# Motor_Driver.net
KiCad netlist of a schematic drawn in Altium Designer
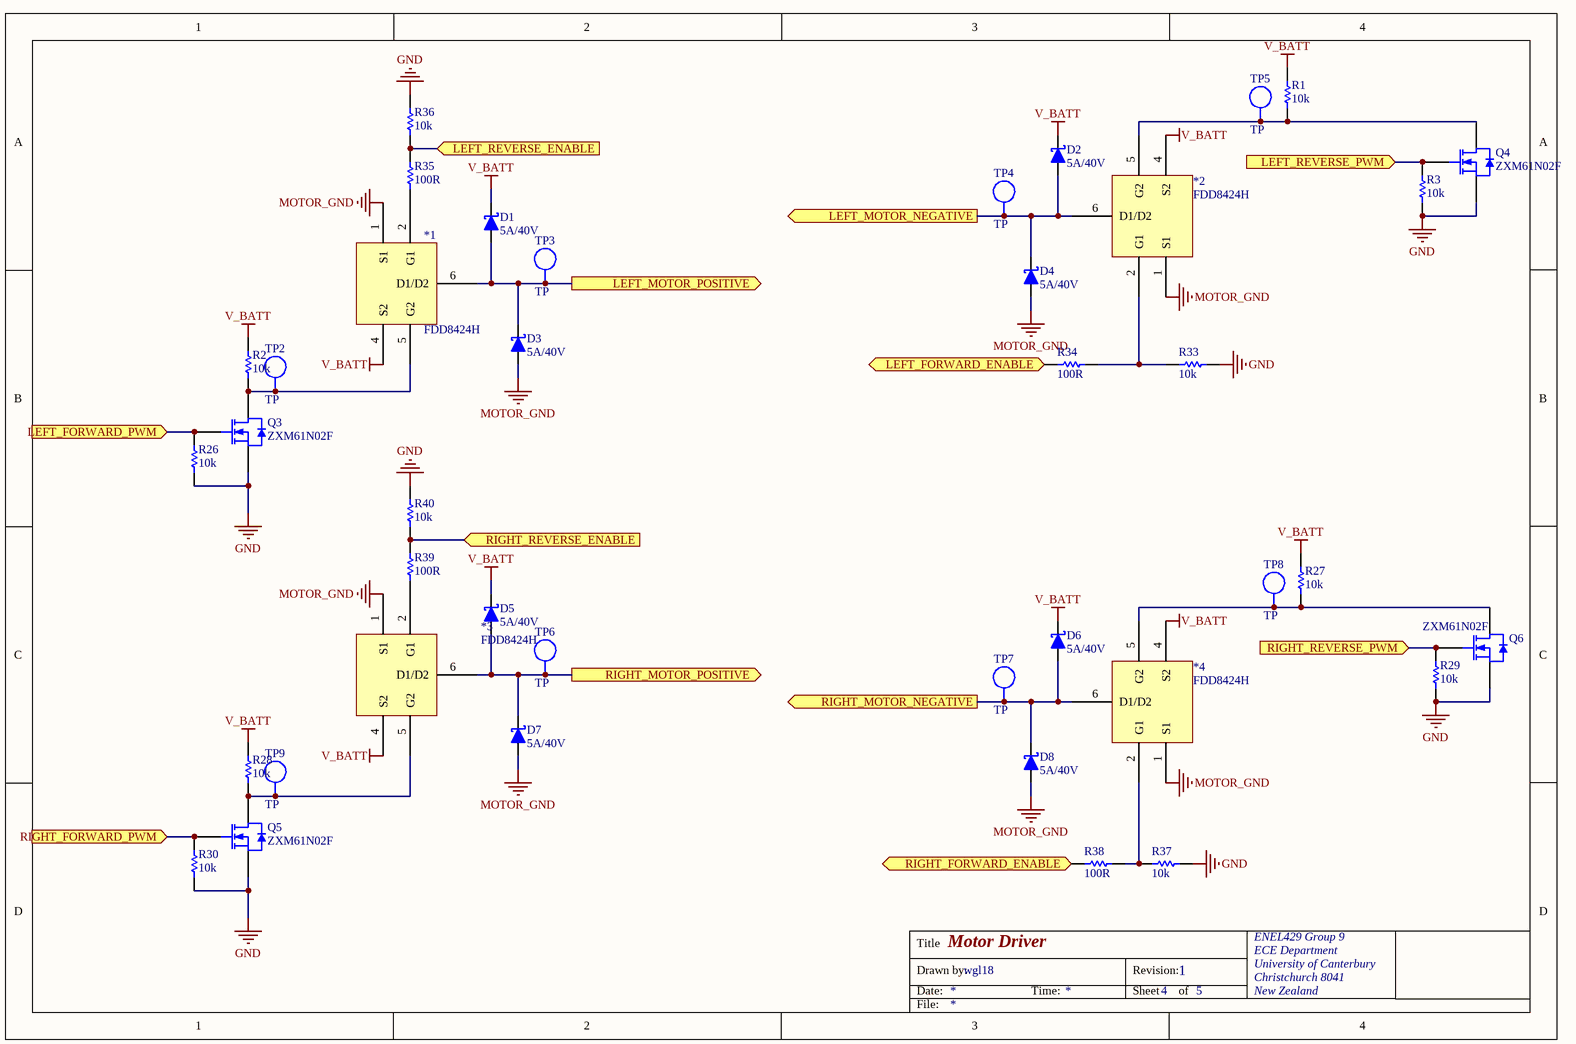
[diagram p0: Motor_Driver.SchDoc]

(export (version "E")
  (design (tool "Eeschema 10.0.6"))
  (components
    (comp (ref "*1")
      (value "FDD8424H")
      (footprint "TO114P990X239-5N")
      (fields (field (name "MANUFACTURER") "Fairchild Semiconductor"))
      (libsource (lib "Wacky_1") (part "FDD8424H"))
    )
    (comp (ref "*2")
      (value "FDD8424H")
      (footprint "TO114P990X239-5N")
      (fields (field (name "MANUFACTURER") "Fairchild Semiconductor"))
      (libsource (lib "") (part "FDD8424H_1"))
    )
    (comp (ref "*3")
      (value "FDD8424H")
      (footprint "TO114P990X239-5N")
      (fields (field (name "MANUFACTURER") "Fairchild Semiconductor"))
      (libsource (lib "Wacky_1") (part "FDD8424H"))
    )
    (comp (ref "*4")
      (value "FDD8424H")
      (footprint "TO114P990X239-5N")
      (fields (field (name "MANUFACTURER") "Fairchild Semiconductor"))
      (libsource (lib "") (part "FDD8424H_1"))
    )
    (comp (ref "D1")
      (value "5A/40V")
      (footprint "DIODE_SMC")
      (description "DIODE SCHOTTKY 5A 40V SMC")
      (fields (field (name "PART NUMBER") "DS_SSC54-E3/57T") (field (name "MANUFACTURER") "Vishay"))
      (libsource (lib "ENEL429_4") (part "DS_SSC54-E3/57T"))
    )
    (comp (ref "D2")
      (value "5A/40V")
      (footprint "DIODE_SMC")
      (description "DIODE SCHOTTKY 5A 40V SMC")
      (fields (field (name "PART NUMBER") "DS_SSC54-E3/57T") (field (name "MANUFACTURER") "Vishay"))
      (libsource (lib "ENEL429_4") (part "DS_SSC54-E3/57T"))
    )
    (comp (ref "D3")
      (value "5A/40V")
      (footprint "DIODE_SMC")
      (description "DIODE SCHOTTKY 5A 40V SMC")
      (fields (field (name "PART NUMBER") "DS_SSC54-E3/57T") (field (name "MANUFACTURER") "Vishay"))
      (libsource (lib "ENEL429_4") (part "DS_SSC54-E3/57T"))
    )
    (comp (ref "D4")
      (value "5A/40V")
      (footprint "DIODE_SMC")
      (description "DIODE SCHOTTKY 5A 40V SMC")
      (fields (field (name "PART NUMBER") "DS_SSC54-E3/57T") (field (name "MANUFACTURER") "Vishay"))
      (libsource (lib "ENEL429_4") (part "DS_SSC54-E3/57T"))
    )
    (comp (ref "D5")
      (value "5A/40V")
      (footprint "DIODE_SMC")
      (description "DIODE SCHOTTKY 5A 40V SMC")
      (fields (field (name "PART NUMBER") "DS_SSC54-E3/57T") (field (name "MANUFACTURER") "Vishay"))
      (libsource (lib "ENEL429_4") (part "DS_SSC54-E3/57T"))
    )
    (comp (ref "D6")
      (value "5A/40V")
      (footprint "DIODE_SMC")
      (description "DIODE SCHOTTKY 5A 40V SMC")
      (fields (field (name "PART NUMBER") "DS_SSC54-E3/57T") (field (name "MANUFACTURER") "Vishay"))
      (libsource (lib "ENEL429_4") (part "DS_SSC54-E3/57T"))
    )
    (comp (ref "D7")
      (value "5A/40V")
      (footprint "DIODE_SMC")
      (description "DIODE SCHOTTKY 5A 40V SMC")
      (fields (field (name "PART NUMBER") "DS_SSC54-E3/57T") (field (name "MANUFACTURER") "Vishay"))
      (libsource (lib "ENEL429_4") (part "DS_SSC54-E3/57T"))
    )
    (comp (ref "D8")
      (value "5A/40V")
      (footprint "DIODE_SMC")
      (description "DIODE SCHOTTKY 5A 40V SMC")
      (fields (field (name "PART NUMBER") "DS_SSC54-E3/57T") (field (name "MANUFACTURER") "Vishay"))
      (libsource (lib "ENEL429_4") (part "DS_SSC54-E3/57T"))
    )
    (comp (ref "Q3")
      (value "ZXM61N02F")
      (footprint "SOT-23")
      (description "20V N-channel enhancement mode MOSFET")
      (fields (field (name "MANUFACTURER") "Zetex") (field (name "PART NUMBER") "TF_ZXM61N02F"))
      (libsource (lib "ENEL429_4") (part "TF_ZXM61N02F"))
    )
    (comp (ref "Q4")
      (value "ZXM61N02F")
      (footprint "SOT-23")
      (description "20V N-channel enhancement mode MOSFET")
      (fields (field (name "MANUFACTURER") "Zetex") (field (name "PART NUMBER") "TF_ZXM61N02F"))
      (libsource (lib "ENEL429_4") (part "TF_ZXM61N02F"))
    )
    (comp (ref "Q5")
      (value "ZXM61N02F")
      (footprint "SOT-23")
      (description "20V N-channel enhancement mode MOSFET")
      (fields (field (name "MANUFACTURER") "Zetex") (field (name "PART NUMBER") "TF_ZXM61N02F"))
      (libsource (lib "ENEL429_4") (part "TF_ZXM61N02F"))
    )
    (comp (ref "Q6")
      (value "ZXM61N02F")
      (footprint "SOT-23")
      (description "20V N-channel enhancement mode MOSFET")
      (fields (field (name "MANUFACTURER") "Zetex") (field (name "PART NUMBER") "TF_ZXM61N02F"))
      (libsource (lib "ENEL429_4") (part "TF_ZXM61N02F"))
    )
    (comp (ref "R1")
      (value "10k")
      (footprint "0603")
      (description "RES 10.0K OHM 1/10W 1% 0603 SMD")
      (fields (field (name "MANUFACTURER") "Yageo") (field (name "PART NUMBER") "RS_10k 0603"))
      (libsource (lib "ENEL429_4") (part "RS_10k 0603"))
    )
    (comp (ref "R2")
      (value "10k")
      (footprint "0603")
      (description "RES 10.0K OHM 1/10W 1% 0603 SMD")
      (fields (field (name "MANUFACTURER") "Yageo") (field (name "PART NUMBER") "RS_10k 0603"))
      (libsource (lib "ENEL429_4") (part "RS_10k 0603"))
    )
    (comp (ref "R3")
      (value "10k")
      (footprint "0603")
      (description "RES 10.0K OHM 1/10W 1% 0603 SMD")
      (fields (field (name "MANUFACTURER") "Yageo") (field (name "PART NUMBER") "RS_10k 0603"))
      (libsource (lib "ENEL429_4") (part "RS_10k 0603"))
    )
    (comp (ref "R26")
      (value "10k")
      (footprint "0603")
      (description "RES 10.0K OHM 1/10W 1% 0603 SMD")
      (fields (field (name "MANUFACTURER") "Yageo") (field (name "PART NUMBER") "RS_10k 0603"))
      (libsource (lib "ENEL429_4") (part "RS_10k 0603"))
    )
    (comp (ref "R27")
      (value "10k")
      (footprint "0603")
      (description "RES 10.0K OHM 1/10W 1% 0603 SMD")
      (fields (field (name "MANUFACTURER") "Yageo") (field (name "PART NUMBER") "RS_10k 0603"))
      (libsource (lib "ENEL429_4") (part "RS_10k 0603"))
    )
    (comp (ref "R28")
      (value "10k")
      (footprint "0603")
      (description "RES 10.0K OHM 1/10W 1% 0603 SMD")
      (fields (field (name "MANUFACTURER") "Yageo") (field (name "PART NUMBER") "RS_10k 0603"))
      (libsource (lib "ENEL429_4") (part "RS_10k 0603"))
    )
    (comp (ref "R29")
      (value "10k")
      (footprint "0603")
      (description "RES 10.0K OHM 1/10W 1% 0603 SMD")
      (fields (field (name "MANUFACTURER") "Yageo") (field (name "PART NUMBER") "RS_10k 0603"))
      (libsource (lib "ENEL429_4") (part "RS_10k 0603"))
    )
    (comp (ref "R30")
      (value "10k")
      (footprint "0603")
      (description "RES 10.0K OHM 1/10W 1% 0603 SMD")
      (fields (field (name "MANUFACTURER") "Yageo") (field (name "PART NUMBER") "RS_10k 0603"))
      (libsource (lib "ENEL429_4") (part "RS_10k 0603"))
    )
    (comp (ref "R33")
      (value "10k")
      (footprint "0603")
      (description "RES 10.0K OHM 1/10W 1% 0603 SMD")
      (fields (field (name "MANUFACTURER") "Yageo") (field (name "PART NUMBER") "RS_10k 0603"))
      (libsource (lib "ENEL429_4") (part "RS_10k 0603"))
    )
    (comp (ref "R34")
      (value "100R")
      (footprint "0603")
      (description "RES 100 OHM 1/10W 1% 0603 SMD")
      (fields (field (name "MANUFACTURER") "ROHM") (field (name "PART NUMBER") "RS_100R 0603"))
      (libsource (lib "ENEL429_4") (part "RS_100R 0603"))
    )
    (comp (ref "R35")
      (value "100R")
      (footprint "0603")
      (description "RES 100 OHM 1/10W 1% 0603 SMD")
      (fields (field (name "MANUFACTURER") "ROHM") (field (name "PART NUMBER") "RS_100R 0603"))
      (libsource (lib "ENEL429_4") (part "RS_100R 0603"))
    )
    (comp (ref "R36")
      (value "10k")
      (footprint "0603")
      (description "RES 10.0K OHM 1/10W 1% 0603 SMD")
      (fields (field (name "MANUFACTURER") "Yageo") (field (name "PART NUMBER") "RS_10k 0603"))
      (libsource (lib "ENEL429_4") (part "RS_10k 0603"))
    )
    (comp (ref "R37")
      (value "10k")
      (footprint "0603")
      (description "RES 10.0K OHM 1/10W 1% 0603 SMD")
      (fields (field (name "MANUFACTURER") "Yageo") (field (name "PART NUMBER") "RS_10k 0603"))
      (libsource (lib "ENEL429_4") (part "RS_10k 0603"))
    )
    (comp (ref "R38")
      (value "100R")
      (footprint "0603")
      (description "RES 100 OHM 1/10W 1% 0603 SMD")
      (fields (field (name "MANUFACTURER") "ROHM") (field (name "PART NUMBER") "RS_100R 0603"))
      (libsource (lib "ENEL429_4") (part "RS_100R 0603"))
    )
    (comp (ref "R39")
      (value "100R")
      (footprint "0603")
      (description "RES 100 OHM 1/10W 1% 0603 SMD")
      (fields (field (name "MANUFACTURER") "ROHM") (field (name "PART NUMBER") "RS_100R 0603"))
      (libsource (lib "ENEL429_4") (part "RS_100R 0603"))
    )
    (comp (ref "R40")
      (value "10k")
      (footprint "0603")
      (description "RES 10.0K OHM 1/10W 1% 0603 SMD")
      (fields (field (name "MANUFACTURER") "Yageo") (field (name "PART NUMBER") "RS_10k 0603"))
      (libsource (lib "ENEL429_4") (part "RS_10k 0603"))
    )
    (comp (ref "TP2")
      (value "TP")
      (footprint "TEST_POINT_4X2MM")
      (description "Test-Point")
      (fields (field (name "PART NUMBER") "TP_TESTPOINT"))
      (libsource (lib "ENEL429_4") (part "TP_TESTPOINT"))
    )
    (comp (ref "TP3")
      (value "TP")
      (footprint "TEST_POINT_4X2MM")
      (description "Test-Point")
      (fields (field (name "PART NUMBER") "TP_TESTPOINT"))
      (libsource (lib "ENEL429_4") (part "TP_TESTPOINT"))
    )
    (comp (ref "TP4")
      (value "TP")
      (footprint "TEST_POINT_4X2MM")
      (description "Test-Point")
      (fields (field (name "PART NUMBER") "TP_TESTPOINT"))
      (libsource (lib "ENEL429_4") (part "TP_TESTPOINT"))
    )
    (comp (ref "TP5")
      (value "TP")
      (footprint "TEST_POINT_4X2MM")
      (description "Test-Point")
      (fields (field (name "PART NUMBER") "TP_TESTPOINT"))
      (libsource (lib "ENEL429_4") (part "TP_TESTPOINT"))
    )
    (comp (ref "TP6")
      (value "TP")
      (footprint "TEST_POINT_4X2MM")
      (description "Test-Point")
      (fields (field (name "PART NUMBER") "TP_TESTPOINT"))
      (libsource (lib "ENEL429_4") (part "TP_TESTPOINT"))
    )
    (comp (ref "TP7")
      (value "TP")
      (footprint "TEST_POINT_4X2MM")
      (description "Test-Point")
      (fields (field (name "PART NUMBER") "TP_TESTPOINT"))
      (libsource (lib "ENEL429_4") (part "TP_TESTPOINT"))
    )
    (comp (ref "TP8")
      (value "TP")
      (footprint "TEST_POINT_4X2MM")
      (description "Test-Point")
      (fields (field (name "PART NUMBER") "TP_TESTPOINT"))
      (libsource (lib "ENEL429_4") (part "TP_TESTPOINT"))
    )
    (comp (ref "TP9")
      (value "TP")
      (footprint "TEST_POINT_4X2MM")
      (description "Test-Point")
      (fields (field (name "PART NUMBER") "TP_TESTPOINT"))
      (libsource (lib "ENEL429_4") (part "TP_TESTPOINT"))
    )
  )
  (nets
    (net (code "1") (name "/LEFT_FORWARD_ENABLE") (class "Default")
      (node (ref "R34") (pin "1") (pinfunction "1_1") (pintype "passive"))
    )
    (net (code "2") (name "/LEFT_FORWARD_PWM") (class "Default")
      (node (ref "Q3") (pin "1") (pinfunction "G_1") (pintype "passive"))
      (node (ref "R26") (pin "1") (pinfunction "1_1") (pintype "passive"))
    )
    (net (code "3") (name "/LEFT_MOTOR_NEGATIVE") (class "Default")
      (node (ref "*2") (pin "6") (pinfunction "D1/D2_6") (pintype "power_in"))
      (node (ref "D2") (pin "1") (pinfunction "A_1") (pintype "passive"))
      (node (ref "D4") (pin "2") (pinfunction "K_2") (pintype "passive"))
      (node (ref "TP4") (pin "1") (pinfunction "1_1") (pintype "passive"))
    )
    (net (code "4") (name "/LEFT_MOTOR_POSITIVE") (class "Default")
      (node (ref "*1") (pin "6") (pinfunction "D1/D2_6") (pintype "power_in"))
      (node (ref "D1") (pin "1") (pinfunction "A_1") (pintype "passive"))
      (node (ref "D3") (pin "2") (pinfunction "K_2") (pintype "passive"))
      (node (ref "TP3") (pin "1") (pinfunction "1_1") (pintype "passive"))
    )
    (net (code "5") (name "/LEFT_REVERSE_ENABLE") (class "Default")
      (node (ref "R35") (pin "2") (pinfunction "2_2") (pintype "passive"))
      (node (ref "R36") (pin "2") (pinfunction "2_2") (pintype "passive"))
    )
    (net (code "6") (name "/LEFT_REVERSE_PWM") (class "Default")
      (node (ref "Q4") (pin "1") (pinfunction "G_1") (pintype "passive"))
      (node (ref "R3") (pin "2") (pinfunction "2_2") (pintype "passive"))
    )
    (net (code "7") (name "/RIGHT_FORWARD_ENABLE") (class "Default")
      (node (ref "R38") (pin "1") (pinfunction "1_1") (pintype "passive"))
    )
    (net (code "8") (name "/RIGHT_FORWARD_PWM") (class "Default")
      (node (ref "Q5") (pin "1") (pinfunction "G_1") (pintype "passive"))
      (node (ref "R30") (pin "1") (pinfunction "1_1") (pintype "passive"))
    )
    (net (code "9") (name "/RIGHT_MOTOR_NEGATIVE") (class "Default")
      (node (ref "*4") (pin "6") (pinfunction "D1/D2_6") (pintype "power_in"))
      (node (ref "D6") (pin "1") (pinfunction "A_1") (pintype "passive"))
      (node (ref "D8") (pin "2") (pinfunction "K_2") (pintype "passive"))
      (node (ref "TP7") (pin "1") (pinfunction "1_1") (pintype "passive"))
    )
    (net (code "10") (name "/RIGHT_MOTOR_POSITIVE") (class "Default")
      (node (ref "*3") (pin "6") (pinfunction "D1/D2_6") (pintype "power_in"))
      (node (ref "D5") (pin "1") (pinfunction "A_1") (pintype "passive"))
      (node (ref "D7") (pin "2") (pinfunction "K_2") (pintype "passive"))
      (node (ref "TP6") (pin "1") (pinfunction "1_1") (pintype "passive"))
    )
    (net (code "11") (name "/RIGHT_REVERSE_ENABLE") (class "Default")
      (node (ref "R39") (pin "2") (pinfunction "2_2") (pintype "passive"))
      (node (ref "R40") (pin "2") (pinfunction "2_2") (pintype "passive"))
    )
    (net (code "12") (name "/RIGHT_REVERSE_PWM") (class "Default")
      (node (ref "Q6") (pin "1") (pinfunction "G_1") (pintype "passive"))
      (node (ref "R29") (pin "2") (pinfunction "2_2") (pintype "passive"))
    )
    (net (code "13") (name "GND") (class "Default")
      (node (ref "Q3") (pin "2") (pinfunction "S_2") (pintype "passive"))
      (node (ref "Q4") (pin "2") (pinfunction "S_2") (pintype "passive"))
      (node (ref "Q5") (pin "2") (pinfunction "S_2") (pintype "passive"))
      (node (ref "Q6") (pin "2") (pinfunction "S_2") (pintype "passive"))
      (node (ref "R26") (pin "2") (pinfunction "2_2") (pintype "passive"))
      (node (ref "R29") (pin "1") (pinfunction "1_1") (pintype "passive"))
      (node (ref "R3") (pin "1") (pinfunction "1_1") (pintype "passive"))
      (node (ref "R30") (pin "2") (pinfunction "2_2") (pintype "passive"))
      (node (ref "R33") (pin "2") (pinfunction "2_2") (pintype "passive"))
      (node (ref "R36") (pin "1") (pinfunction "1_1") (pintype "passive"))
      (node (ref "R37") (pin "2") (pinfunction "2_2") (pintype "passive"))
      (node (ref "R40") (pin "1") (pinfunction "1_1") (pintype "passive"))
    )
    (net (code "14") (name "MOTOR_GND") (class "Default")
      (node (ref "*1") (pin "1") (pinfunction "S1_1") (pintype "power_in"))
      (node (ref "*2") (pin "1") (pinfunction "S1_1") (pintype "power_in"))
      (node (ref "*3") (pin "1") (pinfunction "S1_1") (pintype "power_in"))
      (node (ref "*4") (pin "1") (pinfunction "S1_1") (pintype "power_in"))
      (node (ref "D3") (pin "1") (pinfunction "A_1") (pintype "passive"))
      (node (ref "D4") (pin "1") (pinfunction "A_1") (pintype "passive"))
      (node (ref "D7") (pin "1") (pinfunction "A_1") (pintype "passive"))
      (node (ref "D8") (pin "1") (pinfunction "A_1") (pintype "passive"))
    )
    (net (code "15") (name "Net-(*1-G1)") (class "Default")
      (node (ref "*1") (pin "2") (pinfunction "G1_2") (pintype "passive"))
      (node (ref "R35") (pin "1") (pinfunction "1_1") (pintype "passive"))
    )
    (net (code "16") (name "Net-(*1-G2)") (class "Default")
      (node (ref "*1") (pin "5") (pinfunction "G2_5") (pintype "power_in"))
      (node (ref "Q3") (pin "3") (pinfunction "D_3") (pintype "passive"))
      (node (ref "R2") (pin "2") (pinfunction "2_2") (pintype "passive"))
      (node (ref "TP2") (pin "1") (pinfunction "1_1") (pintype "passive"))
    )
    (net (code "17") (name "Net-(*2-G1)") (class "Default")
      (node (ref "*2") (pin "2") (pinfunction "G1_2") (pintype "passive"))
      (node (ref "R33") (pin "1") (pinfunction "1_1") (pintype "passive"))
      (node (ref "R34") (pin "2") (pinfunction "2_2") (pintype "passive"))
    )
    (net (code "18") (name "Net-(*2-G2)") (class "Default")
      (node (ref "*2") (pin "5") (pinfunction "G2_5") (pintype "power_in"))
      (node (ref "Q4") (pin "3") (pinfunction "D_3") (pintype "passive"))
      (node (ref "R1") (pin "1") (pinfunction "1_1") (pintype "passive"))
      (node (ref "TP5") (pin "1") (pinfunction "1_1") (pintype "passive"))
    )
    (net (code "19") (name "Net-(*3-G1)") (class "Default")
      (node (ref "*3") (pin "2") (pinfunction "G1_2") (pintype "passive"))
      (node (ref "R39") (pin "1") (pinfunction "1_1") (pintype "passive"))
    )
    (net (code "20") (name "Net-(*3-G2)") (class "Default")
      (node (ref "*3") (pin "5") (pinfunction "G2_5") (pintype "power_in"))
      (node (ref "Q5") (pin "3") (pinfunction "D_3") (pintype "passive"))
      (node (ref "R28") (pin "2") (pinfunction "2_2") (pintype "passive"))
      (node (ref "TP9") (pin "1") (pinfunction "1_1") (pintype "passive"))
    )
    (net (code "21") (name "Net-(*4-G1)") (class "Default")
      (node (ref "*4") (pin "2") (pinfunction "G1_2") (pintype "passive"))
      (node (ref "R37") (pin "1") (pinfunction "1_1") (pintype "passive"))
      (node (ref "R38") (pin "2") (pinfunction "2_2") (pintype "passive"))
    )
    (net (code "22") (name "Net-(*4-G2)") (class "Default")
      (node (ref "*4") (pin "5") (pinfunction "G2_5") (pintype "power_in"))
      (node (ref "Q6") (pin "3") (pinfunction "D_3") (pintype "passive"))
      (node (ref "R27") (pin "1") (pinfunction "1_1") (pintype "passive"))
      (node (ref "TP8") (pin "1") (pinfunction "1_1") (pintype "passive"))
    )
    (net (code "23") (name "V_BATT") (class "Default")
      (node (ref "*1") (pin "4") (pinfunction "S2_4") (pintype "power_in"))
      (node (ref "*2") (pin "4") (pinfunction "S2_4") (pintype "power_in"))
      (node (ref "*3") (pin "4") (pinfunction "S2_4") (pintype "power_in"))
      (node (ref "*4") (pin "4") (pinfunction "S2_4") (pintype "power_in"))
      (node (ref "D1") (pin "2") (pinfunction "K_2") (pintype "passive"))
      (node (ref "D2") (pin "2") (pinfunction "K_2") (pintype "passive"))
      (node (ref "D5") (pin "2") (pinfunction "K_2") (pintype "passive"))
      (node (ref "D6") (pin "2") (pinfunction "K_2") (pintype "passive"))
      (node (ref "R1") (pin "2") (pinfunction "2_2") (pintype "passive"))
      (node (ref "R2") (pin "1") (pinfunction "1_1") (pintype "passive"))
      (node (ref "R27") (pin "2") (pinfunction "2_2") (pintype "passive"))
      (node (ref "R28") (pin "1") (pinfunction "1_1") (pintype "passive"))
    )
    (net (code "24") (name "unconnected-(*1-DNC-Pad3)") (class "Default")
      (node (ref "*1") (pin "3") (pinfunction "DNC_3") (pintype "passive"))
    )
    (net (code "25") (name "unconnected-(*2-DNC-Pad3)") (class "Default")
      (node (ref "*2") (pin "3") (pinfunction "DNC_3") (pintype "passive"))
    )
    (net (code "26") (name "unconnected-(*3-DNC-Pad3)") (class "Default")
      (node (ref "*3") (pin "3") (pinfunction "DNC_3") (pintype "passive"))
    )
    (net (code "27") (name "unconnected-(*4-DNC-Pad3)") (class "Default")
      (node (ref "*4") (pin "3") (pinfunction "DNC_3") (pintype "passive"))
    )
  )
)
